# W076oNew.net
KiCad netlist of a schematic drawn in EAGLE
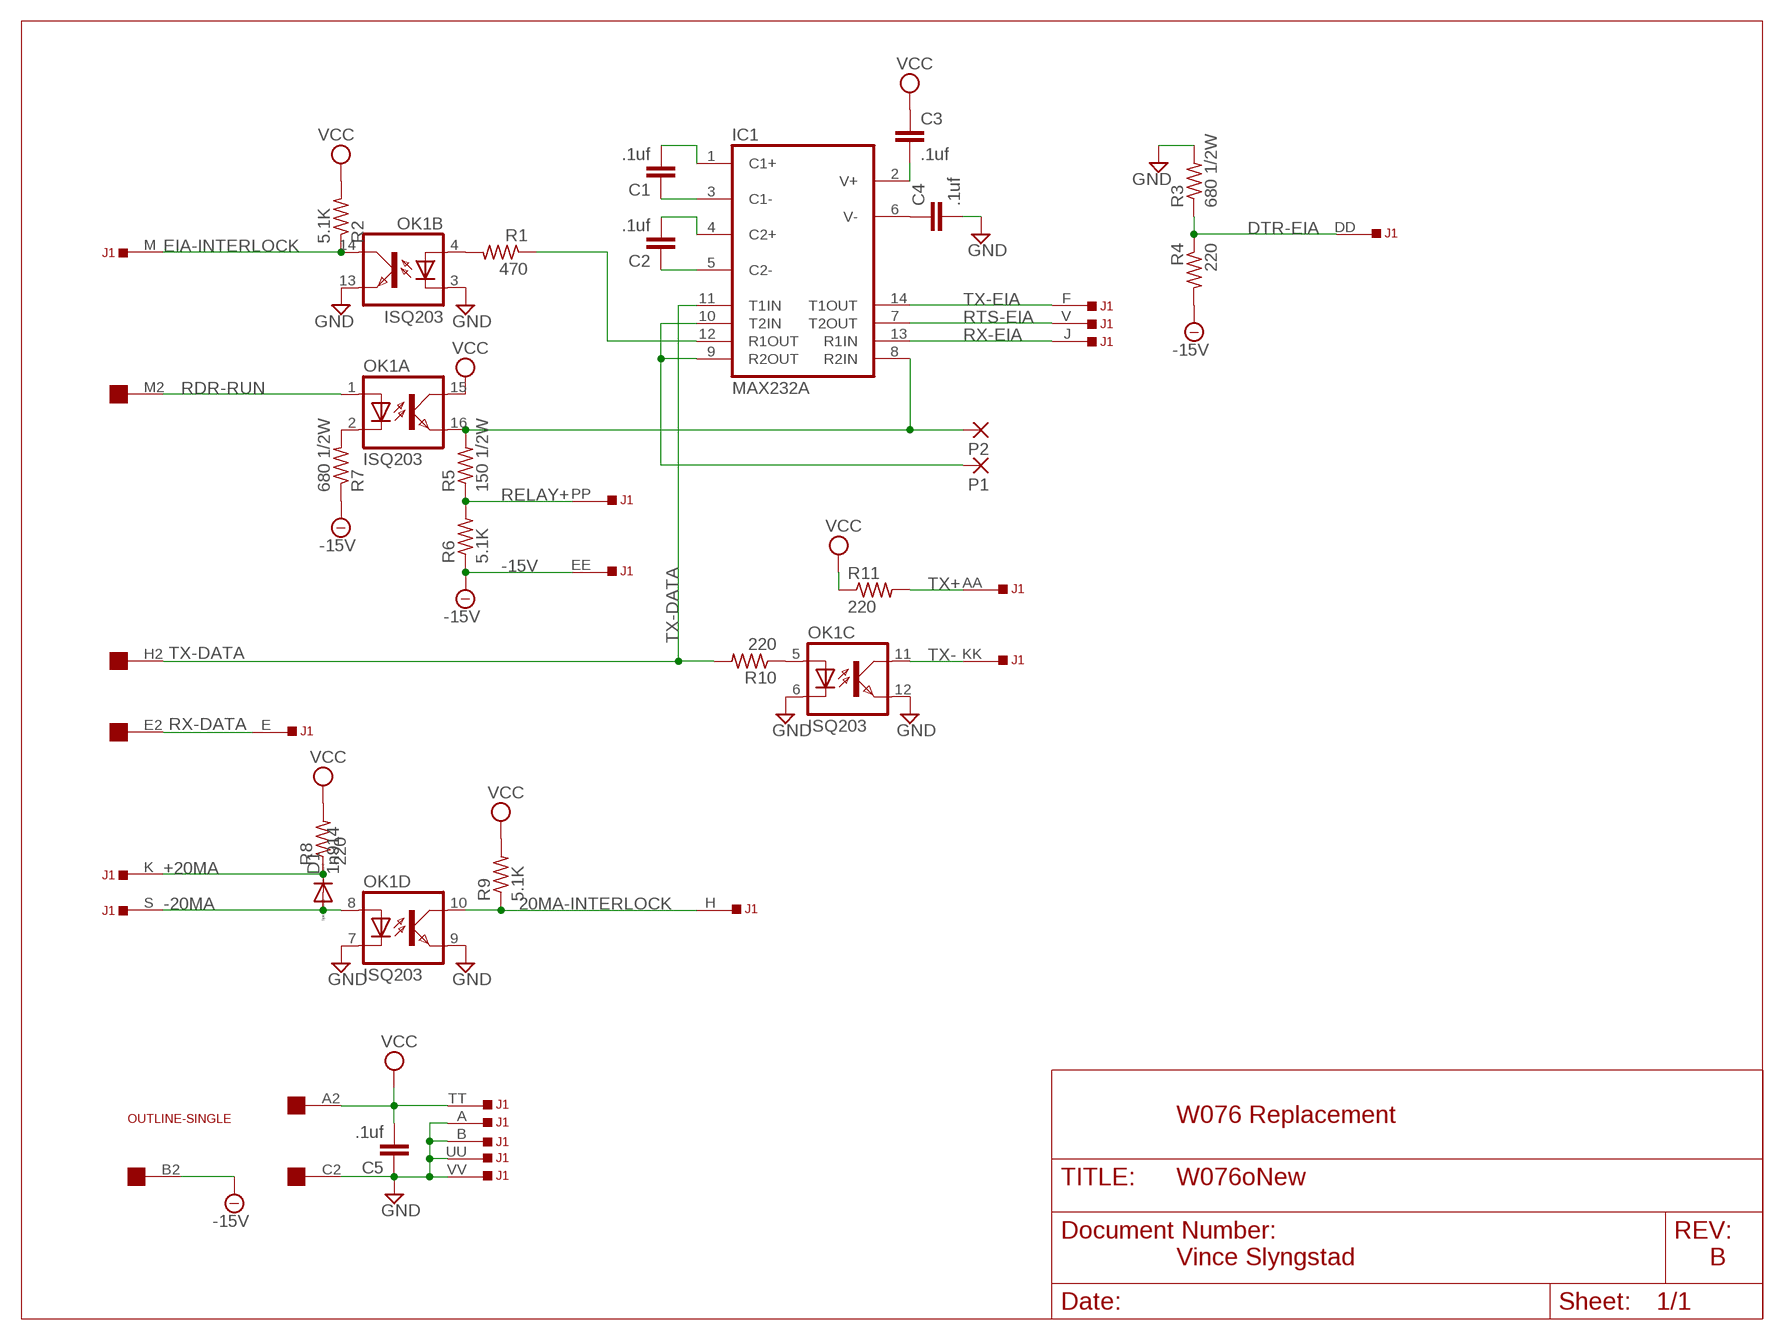
[diagram p0: schematic, sheet 1]

(export (version "E")
  (design (tool "Eeschema 10.0.6"))
  (components
    (comp (ref "C1")
      (value ".1uf")
      (footprint "eagle-import:C050-025X075")
      (libsource (lib "eagle-import") (part "C-EU050-025X075"))
    )
    (comp (ref "C2")
      (value ".1uf")
      (footprint "eagle-import:C050-025X075")
      (libsource (lib "eagle-import") (part "C-EU050-025X075"))
    )
    (comp (ref "C3")
      (value ".1uf")
      (footprint "eagle-import:C050-025X075")
      (libsource (lib "eagle-import") (part "C-EU050-025X075"))
    )
    (comp (ref "C4")
      (value ".1uf")
      (footprint "eagle-import:C050-025X075")
      (libsource (lib "eagle-import") (part "C-EU050-025X075"))
    )
    (comp (ref "C5")
      (value ".1uf")
      (footprint "eagle-import:C050-025X075")
      (libsource (lib "eagle-import") (part "C-EU050-025X075"))
    )
    (comp (ref "D1")
      (value "1n914")
      (footprint "eagle-import:DO41-10")
      (libsource (lib "eagle-import") (part "1N4004"))
    )
    (comp (ref "IC1")
      (value "MAX232A")
      (footprint "eagle-import:DIL16")
      (fields (field (name "MF") "MAXIM") (field (name "MPN") "MAX232ACPE+"))
      (libsource (lib "eagle-import") (part "MAX232"))
    )
    (comp (ref "J1")
      (value "DEC40PINSH")
      (footprint "eagle-import:DEC40PINH")
      (libsource (lib "eagle-import") (part "DEC40PINSH"))
    )
    (comp (ref "OK1")
      (value "ISQ203")
      (footprint "eagle-import:DIL16")
      (fields (field (name "MF") "VISHAY/TELEFUNKEN") (field (name "MPN") "ILQ1"))
      (libsource (lib "eagle-import") (part "ILQ1"))
    )
    (comp (ref "P1")
      (value "1,6/0,8")
      (footprint "eagle-import:1,6_0,8")
      (libsource (lib "eagle-import") (part "1,6/0,8"))
    )
    (comp (ref "P2")
      (value "1,6/0,8")
      (footprint "eagle-import:1,6_0,8")
      (libsource (lib "eagle-import") (part "1,6/0,8"))
    )
    (comp (ref "R1")
      (value "470")
      (footprint "eagle-import:0207_10")
      (libsource (lib "eagle-import") (part "R-US_0207/10"))
    )
    (comp (ref "R2")
      (value "5.1K")
      (footprint "eagle-import:0207_10")
      (libsource (lib "eagle-import") (part "R-US_0207/10"))
    )
    (comp (ref "R3")
      (value "680 1/2W")
      (footprint "eagle-import:0207_12")
      (libsource (lib "eagle-import") (part "R-US_0207/12"))
    )
    (comp (ref "R4")
      (value "220")
      (footprint "eagle-import:0207_10")
      (libsource (lib "eagle-import") (part "R-US_0207/10"))
    )
    (comp (ref "R5")
      (value "150 1/2W")
      (footprint "eagle-import:0207_12")
      (libsource (lib "eagle-import") (part "R-US_0207/12"))
    )
    (comp (ref "R6")
      (value "5.1K")
      (footprint "eagle-import:0207_10")
      (libsource (lib "eagle-import") (part "R-US_0207/10"))
    )
    (comp (ref "R7")
      (value "680 1/2W")
      (footprint "eagle-import:0207_12")
      (libsource (lib "eagle-import") (part "R-US_0207/12"))
    )
    (comp (ref "R8")
      (value "220")
      (footprint "eagle-import:0207_10")
      (libsource (lib "eagle-import") (part "R-US_0207/10"))
    )
    (comp (ref "R9")
      (value "5.1K")
      (footprint "eagle-import:0207_10")
      (libsource (lib "eagle-import") (part "R-US_0207/10"))
    )
    (comp (ref "R10")
      (value "220")
      (footprint "eagle-import:0207_10")
      (libsource (lib "eagle-import") (part "R-US_0207/10"))
    )
    (comp (ref "R11")
      (value "220")
      (footprint "eagle-import:0207_10")
      (libsource (lib "eagle-import") (part "R-US_0207/10"))
    )
    (comp (ref "U$2")
      (value "EDGE-1")
      (footprint "eagle-import:EDGE-CON1")
      (libsource (lib "eagle-import") (part "EDGE-1"))
    )
    (comp (ref "U$3")
      (value "OUTLINE-SINGLE")
      (footprint "eagle-import:SINGLE")
      (libsource (lib "eagle-import") (part "OUTLINE-SINGLE"))
    )
  )
  (nets
    (net (code "1") (name "-15V") (class "Default")
      (node (ref "J1") (pin "EE") (pinfunction "P_EE") (pintype "passive"))
      (node (ref "R4") (pin "2") (pinfunction "2_2") (pintype "passive"))
      (node (ref "R6") (pin "1") (pinfunction "1_1") (pintype "passive"))
      (node (ref "R7") (pin "1") (pinfunction "1_1") (pintype "passive"))
      (node (ref "U$2") (pin "B2") (pinfunction "1_B2") (pintype "bidirectional"))
    )
    (net (code "2") (name "/+20MA") (class "Default")
      (node (ref "D1") (pin "C") (pinfunction "C_C") (pintype "passive"))
      (node (ref "J1") (pin "K") (pinfunction "P_K") (pintype "passive"))
      (node (ref "R8") (pin "1") (pinfunction "1_1") (pintype "passive"))
    )
    (net (code "3") (name "/-20MA") (class "Default")
      (node (ref "D1") (pin "A") (pinfunction "A_A") (pintype "passive"))
      (node (ref "J1") (pin "S") (pinfunction "P_S") (pintype "passive"))
      (node (ref "OK1") (pin "8") (pinfunction "A_8") (pintype "passive"))
    )
    (net (code "4") (name "/20MA-INTERLOCK") (class "Default")
      (node (ref "J1") (pin "H") (pinfunction "P_H") (pintype "passive"))
      (node (ref "OK1") (pin "10") (pinfunction "COL_10") (pintype "passive"))
      (node (ref "R9") (pin "1") (pinfunction "1_1") (pintype "passive"))
    )
    (net (code "5") (name "/DTR-EIA") (class "Default")
      (node (ref "J1") (pin "DD") (pinfunction "P_DD") (pintype "passive"))
      (node (ref "R3") (pin "1") (pinfunction "1_1") (pintype "passive"))
      (node (ref "R4") (pin "1") (pinfunction "1_1") (pintype "passive"))
    )
    (net (code "6") (name "/EIA-INTERLOCK") (class "Default")
      (node (ref "J1") (pin "M") (pinfunction "P_M") (pintype "passive"))
      (node (ref "OK1") (pin "14") (pinfunction "COL_14") (pintype "passive"))
      (node (ref "R2") (pin "1") (pinfunction "1_1") (pintype "passive"))
    )
    (net (code "7") (name "/RDR-RUN") (class "Default")
      (node (ref "OK1") (pin "1") (pinfunction "A_1") (pintype "passive"))
      (node (ref "U$2") (pin "M2") (pinfunction "1_M2") (pintype "bidirectional"))
    )
    (net (code "8") (name "/RELAY+") (class "Default")
      (node (ref "J1") (pin "PP") (pinfunction "P_PP") (pintype "passive"))
      (node (ref "R5") (pin "1") (pinfunction "1_1") (pintype "passive"))
      (node (ref "R6") (pin "2") (pinfunction "2_2") (pintype "passive"))
    )
    (net (code "9") (name "/RTS-EIA") (class "Default")
      (node (ref "IC1") (pin "7") (pinfunction "T2OUT_7") (pintype "output"))
      (node (ref "J1") (pin "V") (pinfunction "P_V") (pintype "passive"))
    )
    (net (code "10") (name "/RX-DATA") (class "Default")
      (node (ref "J1") (pin "E") (pinfunction "P_E") (pintype "passive"))
      (node (ref "U$2") (pin "E2") (pinfunction "1_E2") (pintype "bidirectional"))
    )
    (net (code "11") (name "/RX-EIA") (class "Default")
      (node (ref "IC1") (pin "13") (pinfunction "R1IN_13") (pintype "input"))
      (node (ref "J1") (pin "J") (pinfunction "P_J") (pintype "passive"))
    )
    (net (code "12") (name "/TX+") (class "Default")
      (node (ref "J1") (pin "AA") (pinfunction "P_AA") (pintype "passive"))
      (node (ref "R11") (pin "2") (pinfunction "2_2") (pintype "passive"))
    )
    (net (code "13") (name "/TX-") (class "Default")
      (node (ref "J1") (pin "KK") (pinfunction "P_KK") (pintype "passive"))
      (node (ref "OK1") (pin "11") (pinfunction "COL_11") (pintype "passive"))
    )
    (net (code "14") (name "/TX-DATA") (class "Default")
      (node (ref "IC1") (pin "11") (pinfunction "T1IN_11") (pintype "input"))
      (node (ref "R10") (pin "2") (pinfunction "2_2") (pintype "passive"))
      (node (ref "U$2") (pin "H2") (pinfunction "1_H2") (pintype "bidirectional"))
    )
    (net (code "15") (name "/TX-EIA") (class "Default")
      (node (ref "IC1") (pin "14") (pinfunction "T1OUT_14") (pintype "output"))
      (node (ref "J1") (pin "F") (pinfunction "P_F") (pintype "passive"))
    )
    (net (code "16") (name "GND") (class "Default")
      (node (ref "C4") (pin "2") (pinfunction "2_2") (pintype "passive"))
      (node (ref "C5") (pin "1") (pinfunction "1_1") (pintype "passive"))
      (node (ref "J1") (pin "A") (pinfunction "P_A") (pintype "passive"))
      (node (ref "J1") (pin "B") (pinfunction "P_B") (pintype "passive"))
      (node (ref "J1") (pin "UU") (pinfunction "P_UU") (pintype "passive"))
      (node (ref "J1") (pin "VV") (pinfunction "P_VV") (pintype "passive"))
      (node (ref "OK1") (pin "12") (pinfunction "EMIT_12") (pintype "passive"))
      (node (ref "OK1") (pin "13") (pinfunction "EMIT_13") (pintype "passive"))
      (node (ref "OK1") (pin "3") (pinfunction "C_3") (pintype "passive"))
      (node (ref "OK1") (pin "6") (pinfunction "C_6") (pintype "passive"))
      (node (ref "OK1") (pin "7") (pinfunction "C_7") (pintype "passive"))
      (node (ref "OK1") (pin "9") (pinfunction "EMIT_9") (pintype "passive"))
      (node (ref "R3") (pin "2") (pinfunction "2_2") (pintype "passive"))
      (node (ref "U$2") (pin "C2") (pinfunction "1_C2") (pintype "bidirectional"))
    )
    (net (code "17") (name "Net-(IC1A-C1+)") (class "Default")
      (node (ref "C1") (pin "2") (pinfunction "2_2") (pintype "passive"))
      (node (ref "IC1") (pin "1") (pinfunction "C1+_1") (pintype "bidirectional"))
    )
    (net (code "18") (name "Net-(IC1A-C1-)") (class "Default")
      (node (ref "C1") (pin "1") (pinfunction "1_1") (pintype "passive"))
      (node (ref "IC1") (pin "3") (pinfunction "C1-_3") (pintype "bidirectional"))
    )
    (net (code "19") (name "Net-(IC1A-C2+)") (class "Default")
      (node (ref "C2") (pin "2") (pinfunction "2_2") (pintype "passive"))
      (node (ref "IC1") (pin "4") (pinfunction "C2+_4") (pintype "bidirectional"))
    )
    (net (code "20") (name "Net-(IC1A-C2-)") (class "Default")
      (node (ref "C2") (pin "1") (pinfunction "1_1") (pintype "passive"))
      (node (ref "IC1") (pin "5") (pinfunction "C2-_5") (pintype "bidirectional"))
    )
    (net (code "21") (name "Net-(IC1A-R1OUT)") (class "Default")
      (node (ref "IC1") (pin "12") (pinfunction "R1OUT_12") (pintype "output"))
      (node (ref "R1") (pin "1") (pinfunction "1_1") (pintype "passive"))
    )
    (net (code "22") (name "Net-(IC1A-R2IN)") (class "Default")
      (node (ref "IC1") (pin "8") (pinfunction "R2IN_8") (pintype "input"))
      (node (ref "OK1") (pin "16") (pinfunction "EMIT_16") (pintype "passive"))
      (node (ref "P2") (pin "1") (pinfunction "P_1") (pintype "passive"))
      (node (ref "R5") (pin "2") (pinfunction "2_2") (pintype "passive"))
    )
    (net (code "23") (name "Net-(IC1A-R2OUT)") (class "Default")
      (node (ref "IC1") (pin "10") (pinfunction "T2IN_10") (pintype "input"))
      (node (ref "IC1") (pin "9") (pinfunction "R2OUT_9") (pintype "output"))
      (node (ref "P1") (pin "1") (pinfunction "P_1") (pintype "passive"))
    )
    (net (code "24") (name "Net-(IC1A-V+)") (class "Default")
      (node (ref "C3") (pin "2") (pinfunction "2_2") (pintype "passive"))
      (node (ref "IC1") (pin "2") (pinfunction "V+_2") (pintype "bidirectional"))
    )
    (net (code "25") (name "Net-(IC1A-V-)") (class "Default")
      (node (ref "C4") (pin "1") (pinfunction "1_1") (pintype "passive"))
      (node (ref "IC1") (pin "6") (pinfunction "V-_6") (pintype "bidirectional"))
    )
    (net (code "26") (name "Net-(OK1A-C)") (class "Default")
      (node (ref "OK1") (pin "2") (pinfunction "C_2") (pintype "passive"))
      (node (ref "R7") (pin "2") (pinfunction "2_2") (pintype "passive"))
    )
    (net (code "27") (name "Net-(OK1B-A)") (class "Default")
      (node (ref "OK1") (pin "4") (pinfunction "A_4") (pintype "passive"))
      (node (ref "R1") (pin "2") (pinfunction "2_2") (pintype "passive"))
    )
    (net (code "28") (name "Net-(OK1C-A)") (class "Default")
      (node (ref "OK1") (pin "5") (pinfunction "A_5") (pintype "passive"))
      (node (ref "R10") (pin "1") (pinfunction "1_1") (pintype "passive"))
    )
    (net (code "29") (name "VCC") (class "Default")
      (node (ref "C3") (pin "1") (pinfunction "1_1") (pintype "passive"))
      (node (ref "C5") (pin "2") (pinfunction "2_2") (pintype "passive"))
      (node (ref "J1") (pin "TT") (pinfunction "P_TT") (pintype "passive"))
      (node (ref "OK1") (pin "15") (pinfunction "COL_15") (pintype "passive"))
      (node (ref "R11") (pin "1") (pinfunction "1_1") (pintype "passive"))
      (node (ref "R2") (pin "2") (pinfunction "2_2") (pintype "passive"))
      (node (ref "R8") (pin "2") (pinfunction "2_2") (pintype "passive"))
      (node (ref "R9") (pin "2") (pinfunction "2_2") (pintype "passive"))
      (node (ref "U$2") (pin "A2") (pinfunction "1_A2") (pintype "bidirectional"))
    )
  )
)
